# ODMSpotWelder.net
KiCad netlist of a schematic drawn in EAGLE
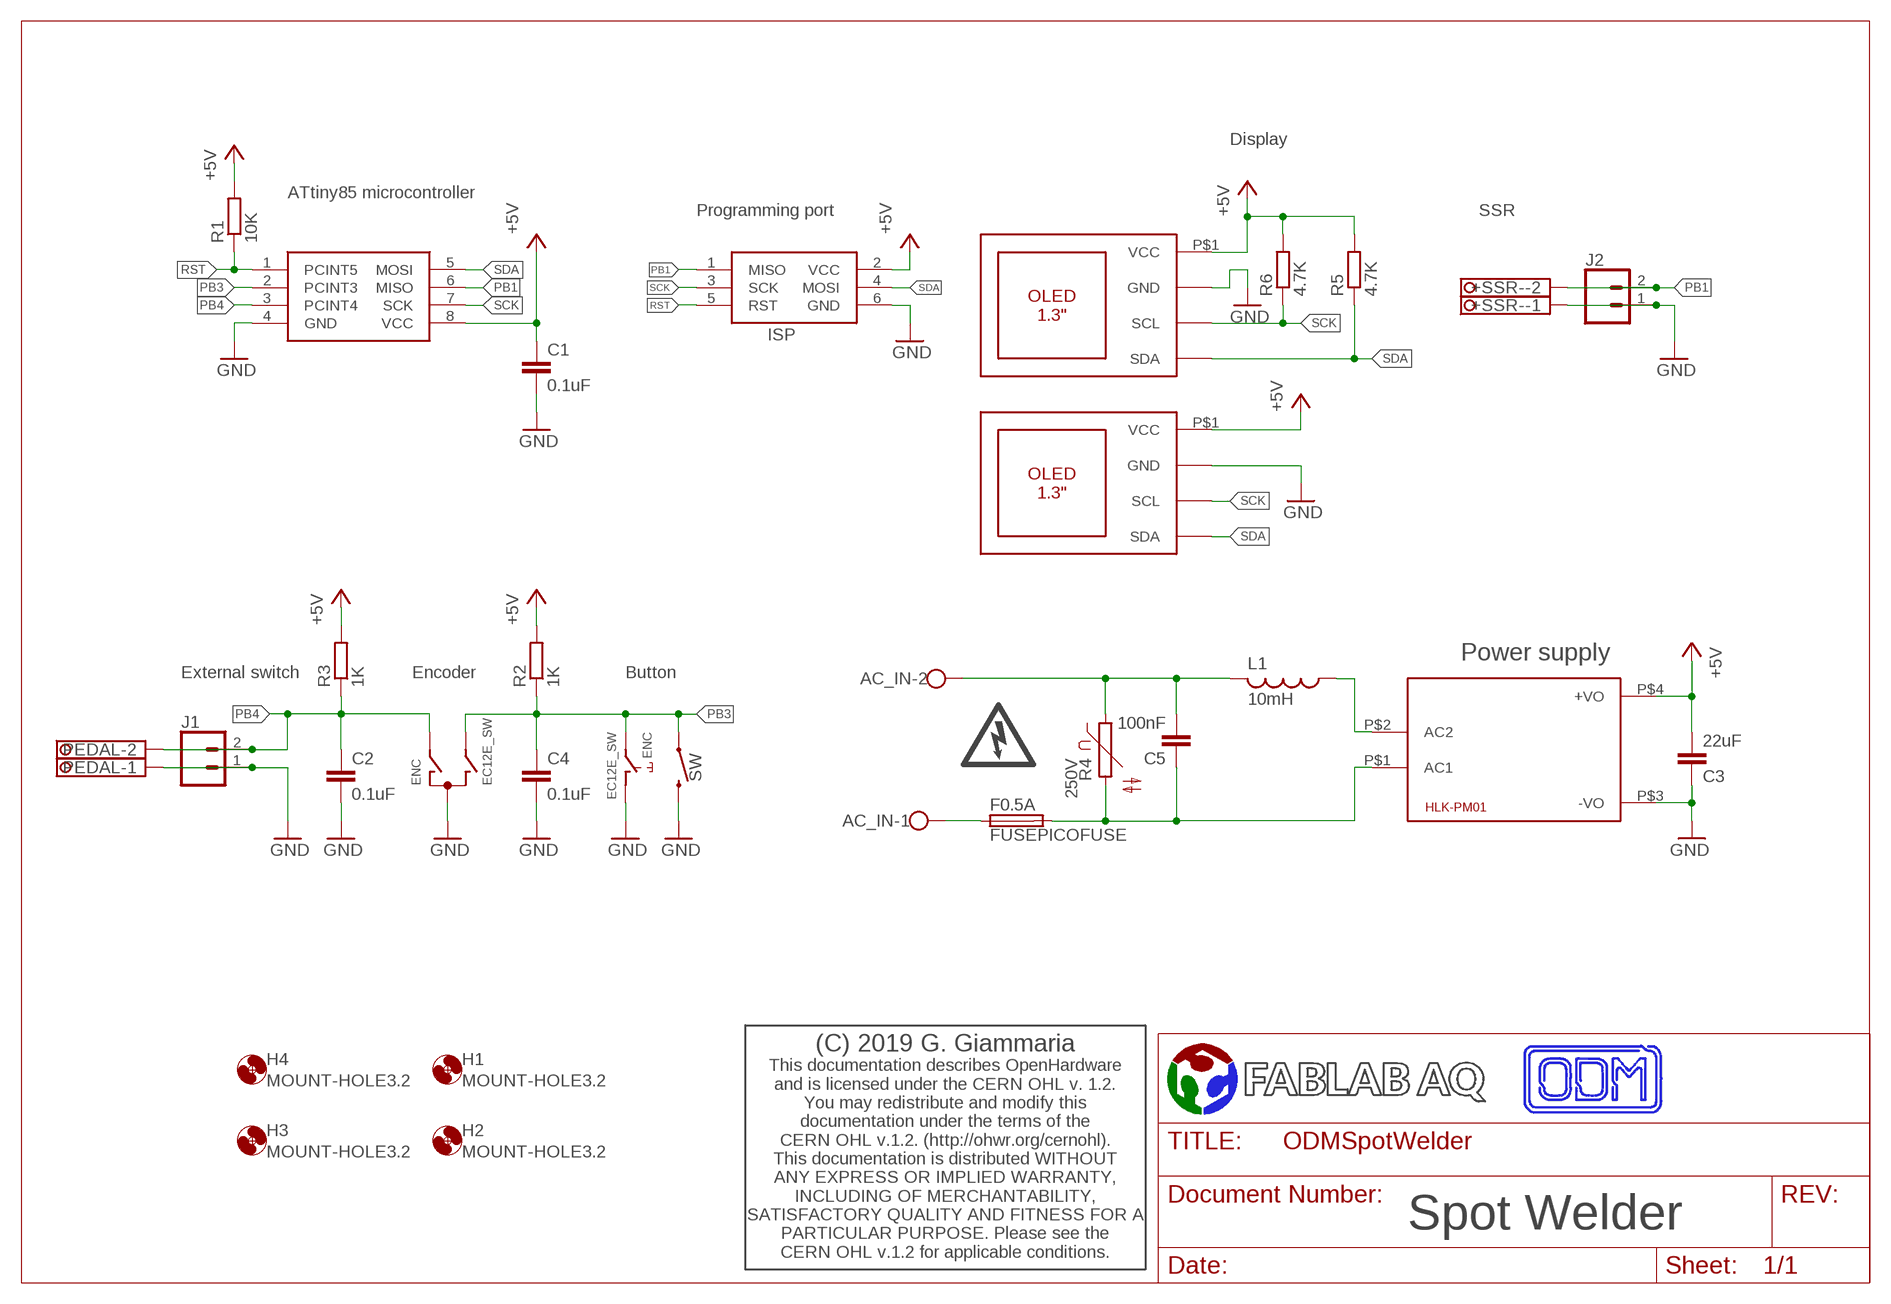
[diagram p0: schematic, sheet 1]

(export (version "E")
  (design (tool "Eeschema 10.0.6"))
  (components
    (comp (ref "+SSR-")
      (value "TERMINAL-BLOCK-3.5MM-2-PIN-LONG-PAD")
      (footprint "eagle-import:TERMINAL-BLOCK-2-PIN-3.5MM-LONG-PAD")
      (libsource (lib "eagle-import") (part "TERMINAL-BLOCK-3.5MM-2-PIN-LONG-PAD"))
    )
    (comp (ref "AC_IN")
      (value "W237-102")
      (footprint "eagle-import:W237-102")
      (fields (field (name "MPN") "237-102"))
      (libsource (lib "eagle-import") (part "W237-102"))
    )
    (comp (ref "C1")
      (value "0.1uF")
      (footprint "eagle-import:C0603K")
      (libsource (lib "eagle-import") (part "C-EUC0603K"))
    )
    (comp (ref "C2")
      (value "0.1uF")
      (footprint "eagle-import:C0603K")
      (libsource (lib "eagle-import") (part "C-EUC0603K"))
    )
    (comp (ref "C3")
      (value "22uF")
      (footprint "eagle-import:C0805K")
      (libsource (lib "eagle-import") (part "C-EUC0805K"))
    )
    (comp (ref "C4")
      (value "0.1uF")
      (footprint "eagle-import:C0603K")
      (libsource (lib "eagle-import") (part "C-EUC0603K"))
    )
    (comp (ref "C5")
      (value "100nF")
      (footprint "eagle-import:C102-064X133")
      (libsource (lib "eagle-import") (part "C-EU102-064X133"))
    )
    (comp (ref "ENC")
      (value "EC12E_SW")
      (footprint "eagle-import:ALPS_EC12E_SW")
      (fields (field (name "MPN") "EC12E2424407"))
      (libsource (lib "eagle-import") (part "EC12E_SW"))
    )
    (comp (ref "F0.5A")
      (value "FUSEPICOFUSE")
      (footprint "eagle-import:PICOFUSE")
      (libsource (lib "eagle-import") (part "FUSEPICOFUSE"))
    )
    (comp (ref "H1")
      (value "MOUNT-HOLE3.2")
      (footprint "eagle-import:3,2")
      (libsource (lib "eagle-import") (part "MOUNT-HOLE3.2"))
    )
    (comp (ref "H2")
      (value "MOUNT-HOLE3.2")
      (footprint "eagle-import:3,2")
      (libsource (lib "eagle-import") (part "MOUNT-HOLE3.2"))
    )
    (comp (ref "H3")
      (value "MOUNT-HOLE3.2")
      (footprint "eagle-import:3,2")
      (libsource (lib "eagle-import") (part "MOUNT-HOLE3.2"))
    )
    (comp (ref "H4")
      (value "MOUNT-HOLE3.2")
      (footprint "eagle-import:3,2")
      (libsource (lib "eagle-import") (part "MOUNT-HOLE3.2"))
    )
    (comp (ref "HLK-PM01")
      (value "HLK-PM01")
      (footprint "eagle-import:HLK-PMXX")
      (libsource (lib "eagle-import") (part "HLK-PMXX3W"))
    )
    (comp (ref "IC2")
      (value "ATTINY85-20SU")
      (footprint "eagle-import:SOT127P798X216-8N")
      (fields
        (field (name "MOUSER_PART_NUMBER") "556-ATTINY85-20SU")
        (field (name "RS_PART_NUMBER") "1331674")
      )
      (libsource (lib "eagle-import") (part "ATTINY85-20SU"))
    )
    (comp (ref "ISP")
      (value "AVRISP-6")
      (footprint "eagle-import:AVRISP")
      (libsource (lib "eagle-import") (part "AVRISP-6"))
    )
    (comp (ref "J1")
      (value "CONN_021X02_NO_SILK")
      (footprint "eagle-import:1X02_NO_SILK")
      (libsource (lib "eagle-import") (part "CONN_021X02_NO_SILK"))
    )
    (comp (ref "J2")
      (value "CONN_021X02_NO_SILK")
      (footprint "eagle-import:1X02_NO_SILK")
      (libsource (lib "eagle-import") (part "CONN_021X02_NO_SILK"))
    )
    (comp (ref "L1")
      (value "10mH")
      (footprint "eagle-import:6000-XXXX-RC")
      (libsource (lib "eagle-import") (part "L-US6000-XXX-RC"))
    )
    (comp (ref "PEDAL")
      (value "TERMINAL-BLOCK-3.5MM-2-PIN-LONG-PAD")
      (footprint "eagle-import:TERMINAL-BLOCK-2-PIN-3.5MM-LONG-PAD")
      (libsource (lib "eagle-import") (part "TERMINAL-BLOCK-3.5MM-2-PIN-LONG-PAD"))
    )
    (comp (ref "R1")
      (value "10K")
      (footprint "eagle-import:R0603")
      (libsource (lib "eagle-import") (part "R-EU_R0603"))
    )
    (comp (ref "R2")
      (value "1K")
      (footprint "eagle-import:R0603")
      (libsource (lib "eagle-import") (part "R-EU_R0603"))
    )
    (comp (ref "R3")
      (value "1K")
      (footprint "eagle-import:R0603")
      (libsource (lib "eagle-import") (part "R-EU_R0603"))
    )
    (comp (ref "R4")
      (value "250V")
      (footprint "eagle-import:S07K250")
      (libsource (lib "eagle-import") (part "S07K250"))
    )
    (comp (ref "R5")
      (value "4.7K")
      (footprint "eagle-import:R0603")
      (libsource (lib "eagle-import") (part "R-EU_R0603"))
    )
    (comp (ref "R6")
      (value "4.7K")
      (footprint "eagle-import:R0603")
      (libsource (lib "eagle-import") (part "R-EU_R0603"))
    )
    (comp (ref "SW")
      (value "MOMENTARY-SWITCH-SPST-PTH-6.0MM")
      (footprint "eagle-import:TACTILE_SWITCH_PTH_6.0MM")
      (libsource (lib "eagle-import") (part "MOMENTARY-SWITCH-SPST-PTH-6.0MM"))
    )
    (comp (ref "U$1")
      (value "(C) 2019 G. Giammaria")
      (footprint "eagle-import:DOC_CERN_OHL_1.2")
      (libsource (lib "eagle-import") (part "CERN_OHL_1.2"))
    )
    (comp (ref "U$2")
      (value "HV_SYMBOL")
      (footprint "eagle-import:HV_SYMBOL_10X10")
      (libsource (lib "eagle-import") (part "HV_SYMBOL"))
    )
    (comp (ref "U$4")
      (value "FABLABAQ_LOGOINLINE_4.5X20")
      (footprint "eagle-import:SILK_INLINE_4.5X20")
      (libsource (lib "eagle-import") (part "FABLABAQ_LOGOINLINE_4.5X20"))
    )
    (comp (ref "U$5")
      (value "ODM_LOGO")
      (footprint "eagle-import:ODM_6X12")
      (libsource (lib "eagle-import") (part "ODM_LOGO"))
    )
    (comp (ref "U$6")
      (value "OLED_1.3_I2C")
      (footprint "eagle-import:OLED_1.3_I2C")
      (libsource (lib "eagle-import") (part "OLED_1.3_I2C"))
    )
    (comp (ref "U$7")
      (value "OLED_1.3_I2C")
      (footprint "eagle-import:OLED_1.3_I2C")
      (libsource (lib "eagle-import") (part "OLED_1.3_I2C"))
    )
  )
  (nets
    (net (code "1") (name "+5V") (class "Default")
      (node (ref "C1") (pin "1") (pinfunction "1_1") (pintype "passive"))
      (node (ref "C3") (pin "2") (pinfunction "2_2") (pintype "passive"))
      (node (ref "HLK-PM01") (pin "P$4") (pinfunction "+VO_P$4") (pintype "bidirectional"))
      (node (ref "IC2") (pin "8") (pinfunction "VCC_8") (pintype "power_in"))
      (node (ref "ISP") (pin "2") (pinfunction "VCC_2") (pintype "power_in"))
      (node (ref "R1") (pin "2") (pinfunction "2_2") (pintype "passive"))
      (node (ref "R2") (pin "2") (pinfunction "2_2") (pintype "passive"))
      (node (ref "R3") (pin "2") (pinfunction "2_2") (pintype "passive"))
      (node (ref "R5") (pin "2") (pinfunction "2_2") (pintype "passive"))
      (node (ref "R6") (pin "2") (pinfunction "2_2") (pintype "passive"))
      (node (ref "U$6") (pin "P$1") (pinfunction "VCC_P$1") (pintype "bidirectional"))
      (node (ref "U$7") (pin "P$1") (pinfunction "VCC_P$1") (pintype "bidirectional"))
    )
    (net (code "2") (name "GND") (class "Default")
      (node (ref "+SSR-") (pin "1") (pinfunction "K_1") (pintype "passive"))
      (node (ref "C1") (pin "2") (pinfunction "2_2") (pintype "passive"))
      (node (ref "C2") (pin "2") (pinfunction "2_2") (pintype "passive"))
      (node (ref "C3") (pin "1") (pinfunction "1_1") (pintype "passive"))
      (node (ref "C4") (pin "2") (pinfunction "2_2") (pintype "passive"))
      (node (ref "ENC") (pin "C") (pinfunction "C_C") (pintype "passive"))
      (node (ref "ENC") (pin "D") (pinfunction "1_D") (pintype "passive"))
      (node (ref "HLK-PM01") (pin "P$3") (pinfunction "-VO_P$3") (pintype "bidirectional"))
      (node (ref "IC2") (pin "4") (pinfunction "GND_4") (pintype "power_in"))
      (node (ref "ISP") (pin "6") (pinfunction "GND_6") (pintype "power_in"))
      (node (ref "J1") (pin "1") (pinfunction "1_1") (pintype "passive"))
      (node (ref "J2") (pin "1") (pinfunction "1_1") (pintype "passive"))
      (node (ref "PEDAL") (pin "1") (pinfunction "K_1") (pintype "passive"))
      (node (ref "SW") (pin "3") (pinfunction "2_3") (pintype "passive"))
      (node (ref "U$6") (pin "P$2") (pinfunction "GND_P$2") (pintype "bidirectional"))
      (node (ref "U$7") (pin "P$2") (pinfunction "GND_P$2") (pintype "bidirectional"))
    )
    (net (code "3") (name "Net-(AC_INA-KL)") (class "Default")
      (node (ref "AC_IN") (pin "1") (pinfunction "KL_1") (pintype "passive"))
      (node (ref "F0.5A") (pin "1") (pinfunction "1_1") (pintype "passive"))
    )
    (net (code "4") (name "Net-(AC_INB-KL)") (class "Default")
      (node (ref "AC_IN") (pin "2") (pinfunction "KL_2") (pintype "passive"))
      (node (ref "C5") (pin "2") (pinfunction "2_2") (pintype "passive"))
      (node (ref "L1") (pin "2") (pinfunction "2_2") (pintype "passive"))
      (node (ref "R4") (pin "1") (pinfunction "1_1") (pintype "passive"))
    )
    (net (code "5") (name "Net-(HLK-PM01-AC1)") (class "Default")
      (node (ref "C5") (pin "1") (pinfunction "1_1") (pintype "passive"))
      (node (ref "F0.5A") (pin "2") (pinfunction "2_2") (pintype "passive"))
      (node (ref "HLK-PM01") (pin "P$1") (pinfunction "AC1_P$1") (pintype "bidirectional"))
      (node (ref "R4") (pin "2") (pinfunction "2_2") (pintype "passive"))
    )
    (net (code "6") (name "Net-(HLK-PM01-AC2)") (class "Default")
      (node (ref "HLK-PM01") (pin "P$2") (pinfunction "AC2_P$2") (pintype "bidirectional"))
      (node (ref "L1") (pin "1") (pinfunction "1_1") (pintype "passive"))
    )
    (net (code "7") (name "PB1") (class "Default")
      (node (ref "+SSR-") (pin "2") (pinfunction "K_2") (pintype "passive"))
      (node (ref "IC2") (pin "6") (pinfunction "MISO_6") (pintype "bidirectional"))
      (node (ref "ISP") (pin "1") (pinfunction "MISO_1") (pintype "input"))
      (node (ref "J2") (pin "2") (pinfunction "2_2") (pintype "passive"))
    )
    (net (code "8") (name "PB3") (class "Default")
      (node (ref "C4") (pin "1") (pinfunction "1_1") (pintype "passive"))
      (node (ref "ENC") (pin "B") (pinfunction "B_B") (pintype "passive"))
      (node (ref "ENC") (pin "E") (pinfunction "2_E") (pintype "passive"))
      (node (ref "IC2") (pin "2") (pinfunction "PCINT3_2") (pintype "bidirectional"))
      (node (ref "R2") (pin "1") (pinfunction "1_1") (pintype "passive"))
      (node (ref "SW") (pin "1") (pinfunction "1_1") (pintype "passive"))
    )
    (net (code "9") (name "PB4") (class "Default")
      (node (ref "C2") (pin "1") (pinfunction "1_1") (pintype "passive"))
      (node (ref "ENC") (pin "A") (pinfunction "A_A") (pintype "passive"))
      (node (ref "IC2") (pin "3") (pinfunction "PCINT4_3") (pintype "bidirectional"))
      (node (ref "J1") (pin "2") (pinfunction "2_2") (pintype "passive"))
      (node (ref "PEDAL") (pin "2") (pinfunction "K_2") (pintype "passive"))
      (node (ref "R3") (pin "1") (pinfunction "1_1") (pintype "passive"))
    )
    (net (code "10") (name "RST") (class "Default")
      (node (ref "IC2") (pin "1") (pinfunction "PCINT5_1") (pintype "bidirectional"))
      (node (ref "ISP") (pin "5") (pinfunction "RST_5") (pintype "output"))
      (node (ref "R1") (pin "1") (pinfunction "1_1") (pintype "passive"))
    )
    (net (code "11") (name "SCK") (class "Default")
      (node (ref "IC2") (pin "7") (pinfunction "SCK_7") (pintype "bidirectional"))
      (node (ref "ISP") (pin "3") (pinfunction "SCK_3") (pintype "output"))
      (node (ref "R6") (pin "1") (pinfunction "1_1") (pintype "passive"))
      (node (ref "U$6") (pin "P$3") (pinfunction "SCL_P$3") (pintype "bidirectional"))
      (node (ref "U$7") (pin "P$3") (pinfunction "SCL_P$3") (pintype "bidirectional"))
    )
    (net (code "12") (name "SDA") (class "Default")
      (node (ref "IC2") (pin "5") (pinfunction "MOSI_5") (pintype "bidirectional"))
      (node (ref "ISP") (pin "4") (pinfunction "MOSI_4") (pintype "output"))
      (node (ref "R5") (pin "1") (pinfunction "1_1") (pintype "passive"))
      (node (ref "U$6") (pin "P$4") (pinfunction "SDA_P$4") (pintype "bidirectional"))
      (node (ref "U$7") (pin "P$4") (pinfunction "SDA_P$4") (pintype "bidirectional"))
    )
  )
)
